# VoltageSensingBoard.net
KiCad netlist of a schematic drawn in EAGLE
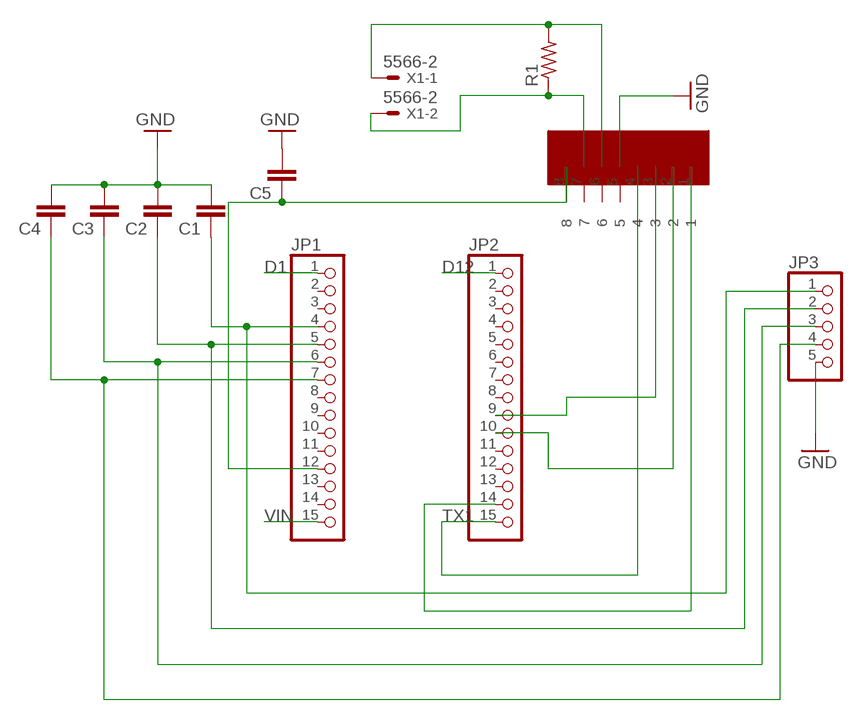
[diagram p0: schematic, sheet 1]

(export (version "E")
  (design (tool "Eeschema 10.0.6"))
  (components
    (comp (ref "C1")
      (value "C5/2.5")
      (footprint "eagle-import:C5B2.5")
      (libsource (lib "eagle-import") (part "C5/2.5"))
    )
    (comp (ref "C2")
      (value "C5/2.5")
      (footprint "eagle-import:C5B2.5")
      (libsource (lib "eagle-import") (part "C5/2.5"))
    )
    (comp (ref "C3")
      (value "C5/2.5")
      (footprint "eagle-import:C5B2.5")
      (libsource (lib "eagle-import") (part "C5/2.5"))
    )
    (comp (ref "C4")
      (value "C5/2.5")
      (footprint "eagle-import:C5B2.5")
      (libsource (lib "eagle-import") (part "C5/2.5"))
    )
    (comp (ref "C5")
      (value "C5/2.5")
      (footprint "eagle-import:C5B2.5")
      (libsource (lib "eagle-import") (part "C5/2.5"))
    )
    (comp (ref "JP1")
      (value "PINHD-1X15")
      (footprint "eagle-import:1X15")
      (libsource (lib "eagle-import") (part "PINHD-1X15"))
    )
    (comp (ref "JP2")
      (value "PINHD-1X15")
      (footprint "eagle-import:1X15")
      (libsource (lib "eagle-import") (part "PINHD-1X15"))
    )
    (comp (ref "JP3")
      (value "PINHD-1X5")
      (footprint "eagle-import:1X05")
      (libsource (lib "eagle-import") (part "PINHD-1X5"))
    )
    (comp (ref "R1")
      (value "R-US_0204/7")
      (footprint "eagle-import:0204_7")
      (libsource (lib "eagle-import") (part "R-US_0204/7"))
    )
    (comp (ref "U$1")
      (value "THVD1550")
      (footprint "eagle-import:SO08")
      (libsource (lib "eagle-import") (part "THVD1550"))
    )
    (comp (ref "X1")
      (value "5566-2")
      (footprint "eagle-import:5566-2")
      (libsource (lib "eagle-import") (part "5566-2"))
    )
  )
  (nets
    (net (code "1") (name "/D1") (class "Default")
      (node (ref "JP1") (pin "1") (pinfunction "1_1") (pintype "passive"))
    )
    (net (code "2") (name "/D12") (class "Default")
      (node (ref "JP2") (pin "1") (pinfunction "1_1") (pintype "passive"))
    )
    (net (code "3") (name "/TX1") (class "Default")
      (node (ref "JP2") (pin "15") (pinfunction "15_15") (pintype "passive"))
      (node (ref "U$1") (pin "4") (pinfunction "4_4") (pintype "bidirectional"))
    )
    (net (code "4") (name "/VIN") (class "Default")
      (node (ref "JP1") (pin "15") (pinfunction "15_15") (pintype "passive"))
    )
    (net (code "5") (name "GND") (class "Default")
      (node (ref "C1") (pin "2") (pinfunction "2_2") (pintype "passive"))
      (node (ref "C2") (pin "2") (pinfunction "2_2") (pintype "passive"))
      (node (ref "C3") (pin "2") (pinfunction "2_2") (pintype "passive"))
      (node (ref "C4") (pin "2") (pinfunction "2_2") (pintype "passive"))
      (node (ref "C5") (pin "2") (pinfunction "2_2") (pintype "passive"))
      (node (ref "JP3") (pin "5") (pinfunction "5_5") (pintype "passive"))
      (node (ref "U$1") (pin "5") (pinfunction "5_5") (pintype "bidirectional"))
    )
    (net (code "6") (name "Net-(C1-Pad1)") (class "Default")
      (node (ref "C1") (pin "1") (pinfunction "1_1") (pintype "passive"))
      (node (ref "JP1") (pin "4") (pinfunction "4_4") (pintype "passive"))
      (node (ref "JP3") (pin "1") (pinfunction "1_1") (pintype "passive"))
    )
    (net (code "7") (name "Net-(C2-Pad1)") (class "Default")
      (node (ref "C2") (pin "1") (pinfunction "1_1") (pintype "passive"))
      (node (ref "JP1") (pin "5") (pinfunction "5_5") (pintype "passive"))
      (node (ref "JP3") (pin "2") (pinfunction "2_2") (pintype "passive"))
    )
    (net (code "8") (name "Net-(C3-Pad1)") (class "Default")
      (node (ref "C3") (pin "1") (pinfunction "1_1") (pintype "passive"))
      (node (ref "JP1") (pin "6") (pinfunction "6_6") (pintype "passive"))
      (node (ref "JP3") (pin "3") (pinfunction "3_3") (pintype "passive"))
    )
    (net (code "9") (name "Net-(C4-Pad1)") (class "Default")
      (node (ref "C4") (pin "1") (pinfunction "1_1") (pintype "passive"))
      (node (ref "JP1") (pin "7") (pinfunction "7_7") (pintype "passive"))
      (node (ref "JP3") (pin "4") (pinfunction "4_4") (pintype "passive"))
    )
    (net (code "10") (name "Net-(C5-Pad1)") (class "Default")
      (node (ref "C5") (pin "1") (pinfunction "1_1") (pintype "passive"))
      (node (ref "JP1") (pin "12") (pinfunction "12_12") (pintype "passive"))
      (node (ref "U$1") (pin "8") (pinfunction "8_8") (pintype "bidirectional"))
    )
    (net (code "11") (name "Net-(JP2-Pad9)") (class "Default")
      (node (ref "JP2") (pin "9") (pinfunction "9_9") (pintype "passive"))
      (node (ref "U$1") (pin "3") (pinfunction "3_3") (pintype "bidirectional"))
    )
    (net (code "12") (name "Net-(JP2-Pad10)") (class "Default")
      (node (ref "JP2") (pin "10") (pinfunction "10_10") (pintype "passive"))
      (node (ref "U$1") (pin "2") (pinfunction "2_2") (pintype "bidirectional"))
    )
    (net (code "13") (name "Net-(JP2-Pad14)") (class "Default")
      (node (ref "JP2") (pin "14") (pinfunction "14_14") (pintype "passive"))
      (node (ref "U$1") (pin "1") (pinfunction "1_1") (pintype "bidirectional"))
    )
    (net (code "14") (name "Net-(X1A-S)") (class "Default")
      (node (ref "R1") (pin "2") (pinfunction "2_2") (pintype "passive"))
      (node (ref "U$1") (pin "6") (pinfunction "6_6") (pintype "bidirectional"))
      (node (ref "X1") (pin "1") (pinfunction "S_1") (pintype "passive"))
    )
    (net (code "15") (name "Net-(X1B-S)") (class "Default")
      (node (ref "R1") (pin "1") (pinfunction "1_1") (pintype "passive"))
      (node (ref "U$1") (pin "7") (pinfunction "7_7") (pintype "bidirectional"))
      (node (ref "X1") (pin "2") (pinfunction "S_2") (pintype "passive"))
    )
    (net (code "16") (name "unconnected-(JP1-Pad2)") (class "Default")
      (node (ref "JP1") (pin "2") (pinfunction "2_2") (pintype "passive"))
    )
    (net (code "17") (name "unconnected-(JP1-Pad3)") (class "Default")
      (node (ref "JP1") (pin "3") (pinfunction "3_3") (pintype "passive"))
    )
    (net (code "18") (name "unconnected-(JP1-Pad8)") (class "Default")
      (node (ref "JP1") (pin "8") (pinfunction "8_8") (pintype "passive"))
    )
    (net (code "19") (name "unconnected-(JP1-Pad9)") (class "Default")
      (node (ref "JP1") (pin "9") (pinfunction "9_9") (pintype "passive"))
    )
    (net (code "20") (name "unconnected-(JP1-Pad10)") (class "Default")
      (node (ref "JP1") (pin "10") (pinfunction "10_10") (pintype "passive"))
    )
    (net (code "21") (name "unconnected-(JP1-Pad11)") (class "Default")
      (node (ref "JP1") (pin "11") (pinfunction "11_11") (pintype "passive"))
    )
    (net (code "22") (name "unconnected-(JP1-Pad13)") (class "Default")
      (node (ref "JP1") (pin "13") (pinfunction "13_13") (pintype "passive"))
    )
    (net (code "23") (name "unconnected-(JP1-Pad14)") (class "Default")
      (node (ref "JP1") (pin "14") (pinfunction "14_14") (pintype "passive"))
    )
    (net (code "24") (name "unconnected-(JP2-Pad2)") (class "Default")
      (node (ref "JP2") (pin "2") (pinfunction "2_2") (pintype "passive"))
    )
    (net (code "25") (name "unconnected-(JP2-Pad3)") (class "Default")
      (node (ref "JP2") (pin "3") (pinfunction "3_3") (pintype "passive"))
    )
    (net (code "26") (name "unconnected-(JP2-Pad4)") (class "Default")
      (node (ref "JP2") (pin "4") (pinfunction "4_4") (pintype "passive"))
    )
    (net (code "27") (name "unconnected-(JP2-Pad5)") (class "Default")
      (node (ref "JP2") (pin "5") (pinfunction "5_5") (pintype "passive"))
    )
    (net (code "28") (name "unconnected-(JP2-Pad6)") (class "Default")
      (node (ref "JP2") (pin "6") (pinfunction "6_6") (pintype "passive"))
    )
    (net (code "29") (name "unconnected-(JP2-Pad7)") (class "Default")
      (node (ref "JP2") (pin "7") (pinfunction "7_7") (pintype "passive"))
    )
    (net (code "30") (name "unconnected-(JP2-Pad8)") (class "Default")
      (node (ref "JP2") (pin "8") (pinfunction "8_8") (pintype "passive"))
    )
    (net (code "31") (name "unconnected-(JP2-Pad11)") (class "Default")
      (node (ref "JP2") (pin "11") (pinfunction "11_11") (pintype "passive"))
    )
    (net (code "32") (name "unconnected-(JP2-Pad12)") (class "Default")
      (node (ref "JP2") (pin "12") (pinfunction "12_12") (pintype "passive"))
    )
    (net (code "33") (name "unconnected-(JP2-Pad13)") (class "Default")
      (node (ref "JP2") (pin "13") (pinfunction "13_13") (pintype "passive"))
    )
  )
)
